# musshca_charles_tp4_2019.net
KiCad netlist of a schematic drawn in EAGLE
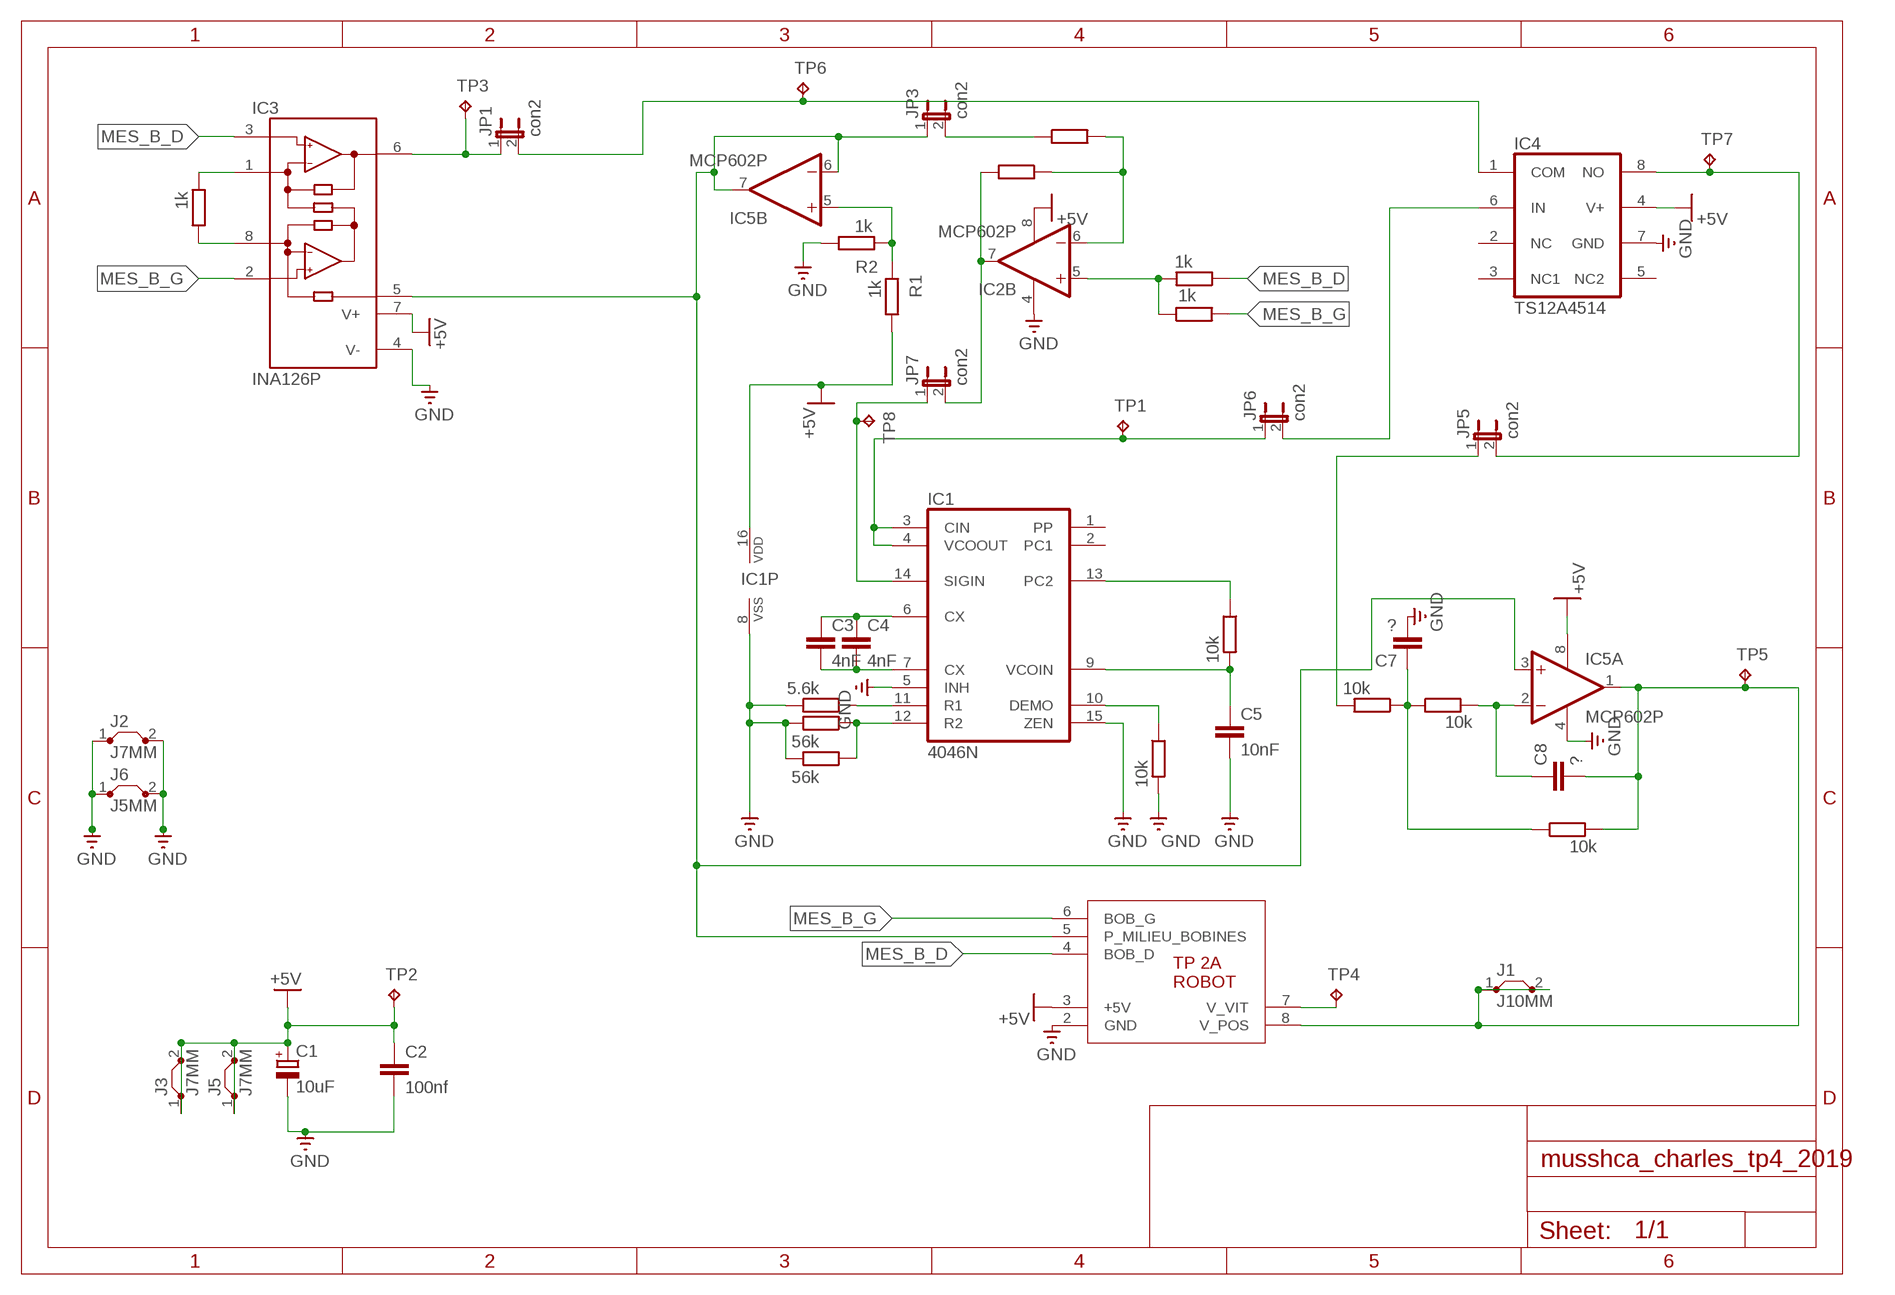
[diagram p0: schematic, sheet 1]

(export (version "E")
  (design (tool "Eeschema 10.0.6"))
  (components
    (comp (ref "C1")
      (value "10uF")
      (footprint "eagle-import:E2,5-7")
      (libsource (lib "eagle-import") (part "CPOL-EUE2.5-7"))
    )
    (comp (ref "C2")
      (value "100nf")
      (footprint "eagle-import:C050-030X075")
      (libsource (lib "eagle-import") (part "C-EU050-030X075"))
    )
    (comp (ref "C3")
      (value "4nF")
      (footprint "eagle-import:C050-030X075")
      (libsource (lib "eagle-import") (part "C-EU050-030X075"))
    )
    (comp (ref "C4")
      (value "4nF")
      (footprint "eagle-import:C050-030X075")
      (libsource (lib "eagle-import") (part "C-EU050-030X075"))
    )
    (comp (ref "C5")
      (value "10nF")
      (footprint "eagle-import:C050-030X075")
      (libsource (lib "eagle-import") (part "C-EU050-030X075"))
    )
    (comp (ref "C7")
      (value "?")
      (footprint "eagle-import:C050-030X075")
      (libsource (lib "eagle-import") (part "C-EU050-030X075"))
    )
    (comp (ref "C8")
      (value "?")
      (footprint "eagle-import:C050-030X075")
      (libsource (lib "eagle-import") (part "C-EU050-030X075"))
    )
    (comp (ref "IC1")
      (value "4046N")
      (footprint "eagle-import:DIL16")
      (libsource (lib "eagle-import") (part "4046N"))
    )
    (comp (ref "IC2")
      (value "MCP602P")
      (footprint "eagle-import:DIL08")
      (libsource (lib "eagle-import") (part "MCP602P"))
    )
    (comp (ref "IC3")
      (value "INA126P")
      (footprint "eagle-import:DIL08")
      (fields (field (name "MF") "TEXAS INSTRUMENT CONNECTORS"))
      (libsource (lib "eagle-import") (part "INA126P"))
    )
    (comp (ref "IC4")
      (value "TS12A4514")
      (footprint "eagle-import:DIL08")
      (fields (field (name "MPN") "TS12A4514PE4"))
      (libsource (lib "eagle-import") (part "TS12A4514"))
    )
    (comp (ref "IC5")
      (value "MCP602P")
      (footprint "eagle-import:DIL08")
      (libsource (lib "eagle-import") (part "MCP602P"))
    )
    (comp (ref "J1")
      (value "J10MM")
      (footprint "eagle-import:10")
      (libsource (lib "eagle-import") (part "J10MM"))
    )
    (comp (ref "J2")
      (value "J7MM")
      (footprint "eagle-import:07")
      (libsource (lib "eagle-import") (part "J7MM"))
    )
    (comp (ref "J3")
      (value "J7MM")
      (footprint "eagle-import:07")
      (libsource (lib "eagle-import") (part "J7MM"))
    )
    (comp (ref "J5")
      (value "J7MM")
      (footprint "eagle-import:07")
      (libsource (lib "eagle-import") (part "J7MM"))
    )
    (comp (ref "J6")
      (value "J5MM")
      (footprint "eagle-import:05")
      (libsource (lib "eagle-import") (part "J5MM"))
    )
    (comp (ref "JP1")
      (value "con2")
      (footprint "eagle-import:JP1")
      (libsource (lib "eagle-import") (part "JP1E"))
    )
    (comp (ref "JP3")
      (value "con2")
      (footprint "eagle-import:JP1")
      (libsource (lib "eagle-import") (part "JP1E"))
    )
    (comp (ref "JP5")
      (value "con2")
      (footprint "eagle-import:JP1")
      (libsource (lib "eagle-import") (part "JP1E"))
    )
    (comp (ref "JP6")
      (value "con2")
      (footprint "eagle-import:JP1")
      (libsource (lib "eagle-import") (part "JP1E"))
    )
    (comp (ref "JP7")
      (value "con2")
      (footprint "eagle-import:JP1")
      (libsource (lib "eagle-import") (part "JP1E"))
    )
    (comp (ref "R1")
      (value "1k")
      (footprint "eagle-import:RC07")
      (libsource (lib "eagle-import") (part "R-EURC07"))
    )
    (comp (ref "R2")
      (value "1k")
      (footprint "eagle-import:RC07")
      (libsource (lib "eagle-import") (part "R-EURC07"))
    )
    (comp (ref "R3")
      (value "1k")
      (footprint "eagle-import:RC07")
      (libsource (lib "eagle-import") (part "R-EURC07"))
    )
    (comp (ref "R4")
      (value "1k")
      (footprint "eagle-import:RC07")
      (libsource (lib "eagle-import") (part "R-EURC07"))
    )
    (comp (ref "R5")
      (value "5.6k")
      (footprint "eagle-import:RC07")
      (libsource (lib "eagle-import") (part "R-EURC07"))
    )
    (comp (ref "R6")
      (value "1k")
      (footprint "eagle-import:RC07")
      (libsource (lib "eagle-import") (part "R-EURC07"))
    )
    (comp (ref "R7")
      (value "1k")
      (footprint "eagle-import:RC07")
      (libsource (lib "eagle-import") (part "R-EURC07"))
    )
    (comp (ref "R8")
      (value "56k")
      (footprint "eagle-import:RC07")
      (libsource (lib "eagle-import") (part "R-EURC07"))
    )
    (comp (ref "R9")
      (value "56k")
      (footprint "eagle-import:RC07")
      (libsource (lib "eagle-import") (part "R-EURC07"))
    )
    (comp (ref "R10")
      (value "10k")
      (footprint "eagle-import:RC07")
      (libsource (lib "eagle-import") (part "R-EURC07"))
    )
    (comp (ref "R11")
      (value "10k")
      (footprint "eagle-import:RC07")
      (libsource (lib "eagle-import") (part "R-EURC07"))
    )
    (comp (ref "R12")
      (value "10k")
      (footprint "eagle-import:RC07")
      (libsource (lib "eagle-import") (part "R-EURC07"))
    )
    (comp (ref "R13")
      (value "10k")
      (footprint "eagle-import:RC07")
      (libsource (lib "eagle-import") (part "R-EURC07"))
    )
    (comp (ref "R14")
      (value "10k")
      (footprint "eagle-import:RC07")
      (libsource (lib "eagle-import") (part "R-EURC07"))
    )
    (comp (ref "RG")
      (value "1k")
      (footprint "eagle-import:RC07")
      (libsource (lib "eagle-import") (part "R-EURC07"))
    )
    (comp (ref "TP1")
      (value "TPPAD1-13")
      (footprint "eagle-import:P1-13")
      (libsource (lib "eagle-import") (part "TPPAD1-13"))
    )
    (comp (ref "TP2")
      (value "TPPAD1-13")
      (footprint "eagle-import:P1-13")
      (libsource (lib "eagle-import") (part "TPPAD1-13"))
    )
    (comp (ref "TP3")
      (value "TPPAD1-13")
      (footprint "eagle-import:P1-13")
      (libsource (lib "eagle-import") (part "TPPAD1-13"))
    )
    (comp (ref "TP4")
      (value "TPPAD1-13")
      (footprint "eagle-import:P1-13")
      (libsource (lib "eagle-import") (part "TPPAD1-13"))
    )
    (comp (ref "TP5")
      (value "TPPAD1-13")
      (footprint "eagle-import:P1-13")
      (libsource (lib "eagle-import") (part "TPPAD1-13"))
    )
    (comp (ref "TP6")
      (value "TPPAD1-13")
      (footprint "eagle-import:P1-13")
      (libsource (lib "eagle-import") (part "TPPAD1-13"))
    )
    (comp (ref "TP7")
      (value "TPPAD1-13")
      (footprint "eagle-import:P1-13")
      (libsource (lib "eagle-import") (part "TPPAD1-13"))
    )
    (comp (ref "TP8")
      (value "TPPAD1-13")
      (footprint "eagle-import:P1-13")
      (libsource (lib "eagle-import") (part "TPPAD1-13"))
    )
    (comp (ref "U$1")
      (value "TP2A_ROBOT")
      (footprint "eagle-import:TP2A_ROBOT")
      (libsource (lib "eagle-import") (part "TP2A_ROBOT"))
    )
  )
  (nets
    (net (code "1") (name "+5V") (class "Default")
      (node (ref "C1") (pin "+") (pinfunction "+_+") (pintype "passive"))
      (node (ref "C2") (pin "1") (pinfunction "1_1") (pintype "passive"))
      (node (ref "IC1") (pin "16") (pinfunction "VDD_16") (pintype "power_in"))
      (node (ref "IC2") (pin "8") (pinfunction "V+_8") (pintype "power_in"))
      (node (ref "IC3") (pin "7") (pinfunction "V+_7") (pintype "power_in"))
      (node (ref "IC4") (pin "4") (pinfunction "V+_4") (pintype "power_in"))
      (node (ref "IC5") (pin "8") (pinfunction "V+_8") (pintype "power_in"))
      (node (ref "J3") (pin "1") (pinfunction "1_1") (pintype "passive"))
      (node (ref "J3") (pin "2") (pinfunction "2_2") (pintype "passive"))
      (node (ref "J5") (pin "1") (pinfunction "1_1") (pintype "passive"))
      (node (ref "J5") (pin "2") (pinfunction "2_2") (pintype "passive"))
      (node (ref "R1") (pin "P$2") (pinfunction "2_P$2") (pintype "passive"))
      (node (ref "TP2") (pin "TP") (pinfunction "TP_TP") (pintype "input"))
      (node (ref "U$1") (pin "3") (pinfunction "+5V_3") (pintype "power_in"))
    )
    (net (code "2") (name "GND") (class "Default")
      (node (ref "C1") (pin "-") (pinfunction "-_-") (pintype "passive"))
      (node (ref "C2") (pin "2") (pinfunction "2_2") (pintype "passive"))
      (node (ref "C5") (pin "2") (pinfunction "2_2") (pintype "passive"))
      (node (ref "C7") (pin "2") (pinfunction "2_2") (pintype "passive"))
      (node (ref "IC1") (pin "15") (pinfunction "ZEN_15") (pintype "input"))
      (node (ref "IC1") (pin "5") (pinfunction "INH_5") (pintype "input"))
      (node (ref "IC1") (pin "8") (pinfunction "VSS_8") (pintype "power_in"))
      (node (ref "IC2") (pin "4") (pinfunction "V-_4") (pintype "power_in"))
      (node (ref "IC3") (pin "4") (pinfunction "V-_4") (pintype "power_in"))
      (node (ref "IC4") (pin "7") (pinfunction "GND_7") (pintype "power_in"))
      (node (ref "IC5") (pin "4") (pinfunction "V-_4") (pintype "power_in"))
      (node (ref "J2") (pin "1") (pinfunction "1_1") (pintype "passive"))
      (node (ref "J2") (pin "2") (pinfunction "2_2") (pintype "passive"))
      (node (ref "J6") (pin "1") (pinfunction "1_1") (pintype "passive"))
      (node (ref "J6") (pin "2") (pinfunction "2_2") (pintype "passive"))
      (node (ref "R11") (pin "P$2") (pinfunction "2_P$2") (pintype "passive"))
      (node (ref "R2") (pin "P$2") (pinfunction "2_P$2") (pintype "passive"))
      (node (ref "R5") (pin "P$2") (pinfunction "2_P$2") (pintype "passive"))
      (node (ref "R8") (pin "P$2") (pinfunction "2_P$2") (pintype "passive"))
      (node (ref "R9") (pin "P$2") (pinfunction "2_P$2") (pintype "passive"))
      (node (ref "U$1") (pin "2") (pinfunction "GND_2") (pintype "power_in"))
    )
    (net (code "3") (name "MES_B_D") (class "Default")
      (node (ref "IC3") (pin "3") (pinfunction "+IN_3") (pintype "input"))
      (node (ref "R3") (pin "P$1") (pinfunction "1_P$1") (pintype "passive"))
      (node (ref "U$1") (pin "4") (pinfunction "BOB_D_4") (pintype "passive"))
    )
    (net (code "4") (name "MES_B_G") (class "Default")
      (node (ref "IC3") (pin "2") (pinfunction "-IN_2") (pintype "input"))
      (node (ref "R4") (pin "P$2") (pinfunction "2_P$2") (pintype "passive"))
      (node (ref "U$1") (pin "6") (pinfunction "BOB_G_6") (pintype "passive"))
    )
    (net (code "5") (name "Net-(C3-Pad1)") (class "Default")
      (node (ref "C3") (pin "1") (pinfunction "1_1") (pintype "passive"))
      (node (ref "C4") (pin "1") (pinfunction "1_1") (pintype "passive"))
      (node (ref "IC1") (pin "6") (pinfunction "CX_6") (pintype "input"))
    )
    (net (code "6") (name "Net-(C3-Pad2)") (class "Default")
      (node (ref "C3") (pin "2") (pinfunction "2_2") (pintype "passive"))
      (node (ref "C4") (pin "2") (pinfunction "2_2") (pintype "passive"))
      (node (ref "IC1") (pin "7") (pinfunction "CX_7") (pintype "input"))
    )
    (net (code "7") (name "Net-(IC1A-CIN)") (class "Default")
      (node (ref "IC1") (pin "3") (pinfunction "CIN_3") (pintype "input"))
      (node (ref "IC1") (pin "4") (pinfunction "VCOOUT_4") (pintype "output"))
      (node (ref "JP6") (pin "1") (pinfunction "1_1") (pintype "passive"))
      (node (ref "TP1") (pin "TP") (pinfunction "TP_TP") (pintype "input"))
    )
    (net (code "8") (name "Net-(IC1A-DEMO)") (class "Default")
      (node (ref "IC1") (pin "10") (pinfunction "DEMO_10") (pintype "output"))
      (node (ref "R11") (pin "P$1") (pinfunction "1_P$1") (pintype "passive"))
    )
    (net (code "9") (name "Net-(IC1A-PC2)") (class "Default")
      (node (ref "IC1") (pin "13") (pinfunction "PC2_13") (pintype "output"))
      (node (ref "R10") (pin "P$1") (pinfunction "1_P$1") (pintype "passive"))
    )
    (net (code "10") (name "Net-(IC1A-R1)") (class "Default")
      (node (ref "IC1") (pin "11") (pinfunction "R1_11") (pintype "input"))
      (node (ref "R5") (pin "P$1") (pinfunction "1_P$1") (pintype "passive"))
    )
    (net (code "11") (name "Net-(IC1A-R2)") (class "Default")
      (node (ref "IC1") (pin "12") (pinfunction "R2_12") (pintype "input"))
      (node (ref "R8") (pin "P$1") (pinfunction "1_P$1") (pintype "passive"))
      (node (ref "R9") (pin "P$1") (pinfunction "1_P$1") (pintype "passive"))
    )
    (net (code "12") (name "Net-(IC1A-SIGIN)") (class "Default")
      (node (ref "IC1") (pin "14") (pinfunction "SIGIN_14") (pintype "input"))
      (node (ref "JP7") (pin "1") (pinfunction "1_1") (pintype "passive"))
      (node (ref "TP8") (pin "TP") (pinfunction "TP_TP") (pintype "input"))
    )
    (net (code "13") (name "Net-(IC1A-VCOIN)") (class "Default")
      (node (ref "C5") (pin "1") (pinfunction "1_1") (pintype "passive"))
      (node (ref "IC1") (pin "9") (pinfunction "VCOIN_9") (pintype "input"))
      (node (ref "R10") (pin "P$2") (pinfunction "2_P$2") (pintype "passive"))
    )
    (net (code "14") (name "Net-(IC2B-+IN)") (class "Default")
      (node (ref "IC2") (pin "5") (pinfunction "+IN_5") (pintype "input"))
      (node (ref "R3") (pin "P$2") (pinfunction "2_P$2") (pintype "passive"))
      (node (ref "R4") (pin "P$1") (pinfunction "1_P$1") (pintype "passive"))
    )
    (net (code "15") (name "Net-(IC2B--IN)") (class "Default")
      (node (ref "IC2") (pin "6") (pinfunction "-IN_6") (pintype "input"))
      (node (ref "R6") (pin "P$1") (pinfunction "1_P$1") (pintype "passive"))
      (node (ref "R7") (pin "P$2") (pinfunction "2_P$2") (pintype "passive"))
    )
    (net (code "16") (name "Net-(IC2B-OUT)") (class "Default")
      (node (ref "IC2") (pin "7") (pinfunction "OUT_7") (pintype "output"))
      (node (ref "JP7") (pin "2") (pinfunction "2_2") (pintype "passive"))
      (node (ref "R6") (pin "P$2") (pinfunction "2_P$2") (pintype "passive"))
    )
    (net (code "17") (name "Net-(IC3-OUT)") (class "Default")
      (node (ref "IC3") (pin "6") (pinfunction "OUT_6") (pintype "output"))
      (node (ref "JP1") (pin "1") (pinfunction "1_1") (pintype "passive"))
      (node (ref "TP3") (pin "TP") (pinfunction "TP_TP") (pintype "input"))
    )
    (net (code "18") (name "Net-(IC3-REF)") (class "Default")
      (node (ref "IC3") (pin "5") (pinfunction "REF_5") (pintype "passive"))
      (node (ref "IC5") (pin "3") (pinfunction "+IN_3") (pintype "input"))
      (node (ref "IC5") (pin "6") (pinfunction "-IN_6") (pintype "input"))
      (node (ref "IC5") (pin "7") (pinfunction "OUT_7") (pintype "output"))
      (node (ref "JP3") (pin "1") (pinfunction "1_1") (pintype "passive"))
      (node (ref "U$1") (pin "5") (pinfunction "P_MILIEU_BOBINES_5") (pintype "passive"))
    )
    (net (code "19") (name "Net-(IC4-COM)") (class "Default")
      (node (ref "IC4") (pin "1") (pinfunction "COM_1") (pintype "passive"))
      (node (ref "JP1") (pin "2") (pinfunction "2_2") (pintype "passive"))
      (node (ref "TP6") (pin "TP") (pinfunction "TP_TP") (pintype "input"))
    )
    (net (code "20") (name "Net-(IC4-IN)") (class "Default")
      (node (ref "IC4") (pin "6") (pinfunction "IN_6") (pintype "input"))
      (node (ref "JP6") (pin "2") (pinfunction "2_2") (pintype "passive"))
    )
    (net (code "21") (name "Net-(IC4-NO)") (class "Default")
      (node (ref "IC4") (pin "8") (pinfunction "NO_8") (pintype "passive"))
      (node (ref "JP5") (pin "2") (pinfunction "2_2") (pintype "passive"))
      (node (ref "TP7") (pin "TP") (pinfunction "TP_TP") (pintype "input"))
    )
    (net (code "22") (name "Net-(IC5A--IN)") (class "Default")
      (node (ref "C8") (pin "1") (pinfunction "1_1") (pintype "passive"))
      (node (ref "IC5") (pin "2") (pinfunction "-IN_2") (pintype "input"))
      (node (ref "R12") (pin "P$2") (pinfunction "2_P$2") (pintype "passive"))
    )
    (net (code "23") (name "Net-(IC5A-OUT)") (class "Default")
      (node (ref "C8") (pin "2") (pinfunction "2_2") (pintype "passive"))
      (node (ref "IC5") (pin "1") (pinfunction "OUT_1") (pintype "output"))
      (node (ref "J1") (pin "1") (pinfunction "1_1") (pintype "passive"))
      (node (ref "J1") (pin "2") (pinfunction "2_2") (pintype "passive"))
      (node (ref "R14") (pin "P$2") (pinfunction "2_P$2") (pintype "passive"))
      (node (ref "TP5") (pin "TP") (pinfunction "TP_TP") (pintype "input"))
      (node (ref "U$1") (pin "8") (pinfunction "V_POS_8") (pintype "passive"))
    )
    (net (code "24") (name "Net-(IC5B-+IN)") (class "Default")
      (node (ref "IC5") (pin "5") (pinfunction "+IN_5") (pintype "input"))
      (node (ref "R1") (pin "P$1") (pinfunction "1_P$1") (pintype "passive"))
      (node (ref "R2") (pin "P$1") (pinfunction "1_P$1") (pintype "passive"))
    )
    (net (code "25") (name "Net-(R7-1)") (class "Default")
      (node (ref "JP3") (pin "2") (pinfunction "2_2") (pintype "passive"))
      (node (ref "R7") (pin "P$1") (pinfunction "1_P$1") (pintype "passive"))
    )
    (net (code "26") (name "Net-(R12-1)") (class "Default")
      (node (ref "C7") (pin "1") (pinfunction "1_1") (pintype "passive"))
      (node (ref "R12") (pin "P$1") (pinfunction "1_P$1") (pintype "passive"))
      (node (ref "R13") (pin "P$1") (pinfunction "1_P$1") (pintype "passive"))
      (node (ref "R14") (pin "P$1") (pinfunction "1_P$1") (pintype "passive"))
    )
    (net (code "27") (name "Net-(R13-2)") (class "Default")
      (node (ref "JP5") (pin "1") (pinfunction "1_1") (pintype "passive"))
      (node (ref "R13") (pin "P$2") (pinfunction "2_P$2") (pintype "passive"))
    )
    (net (code "28") (name "Net-(RG-1)") (class "Default")
      (node (ref "IC3") (pin "1") (pinfunction "RG_1") (pintype "passive"))
      (node (ref "RG") (pin "P$1") (pinfunction "1_P$1") (pintype "passive"))
    )
    (net (code "29") (name "Net-(RG-2)") (class "Default")
      (node (ref "IC3") (pin "8") (pinfunction "RG_8") (pintype "passive"))
      (node (ref "RG") (pin "P$2") (pinfunction "2_P$2") (pintype "passive"))
    )
    (net (code "30") (name "Net-(U$1-V_VIT)") (class "Default")
      (node (ref "TP4") (pin "TP") (pinfunction "TP_TP") (pintype "input"))
      (node (ref "U$1") (pin "7") (pinfunction "V_VIT_7") (pintype "passive"))
    )
    (net (code "31") (name "unconnected-(IC1A-PC1-Pad2)") (class "Default")
      (node (ref "IC1") (pin "2") (pinfunction "PC1_2") (pintype "output"))
    )
    (net (code "32") (name "unconnected-(IC1A-PP-Pad1)") (class "Default")
      (node (ref "IC1") (pin "1") (pinfunction "PP_1") (pintype "output"))
    )
    (net (code "33") (name "unconnected-(IC4-NC-Pad2)") (class "Default")
      (node (ref "IC4") (pin "2") (pinfunction "NC_2") (pintype "no_connect"))
    )
    (net (code "34") (name "unconnected-(IC4-NC1-Pad3)") (class "Default")
      (node (ref "IC4") (pin "3") (pinfunction "NC1_3") (pintype "no_connect"))
    )
    (net (code "35") (name "unconnected-(IC4-NC2-Pad5)") (class "Default")
      (node (ref "IC4") (pin "5") (pinfunction "NC2_5") (pintype "no_connect"))
    )
  )
)
